# 467444_130_3_2-A.net
KiCad netlist of a schematic drawn in Altium Designer
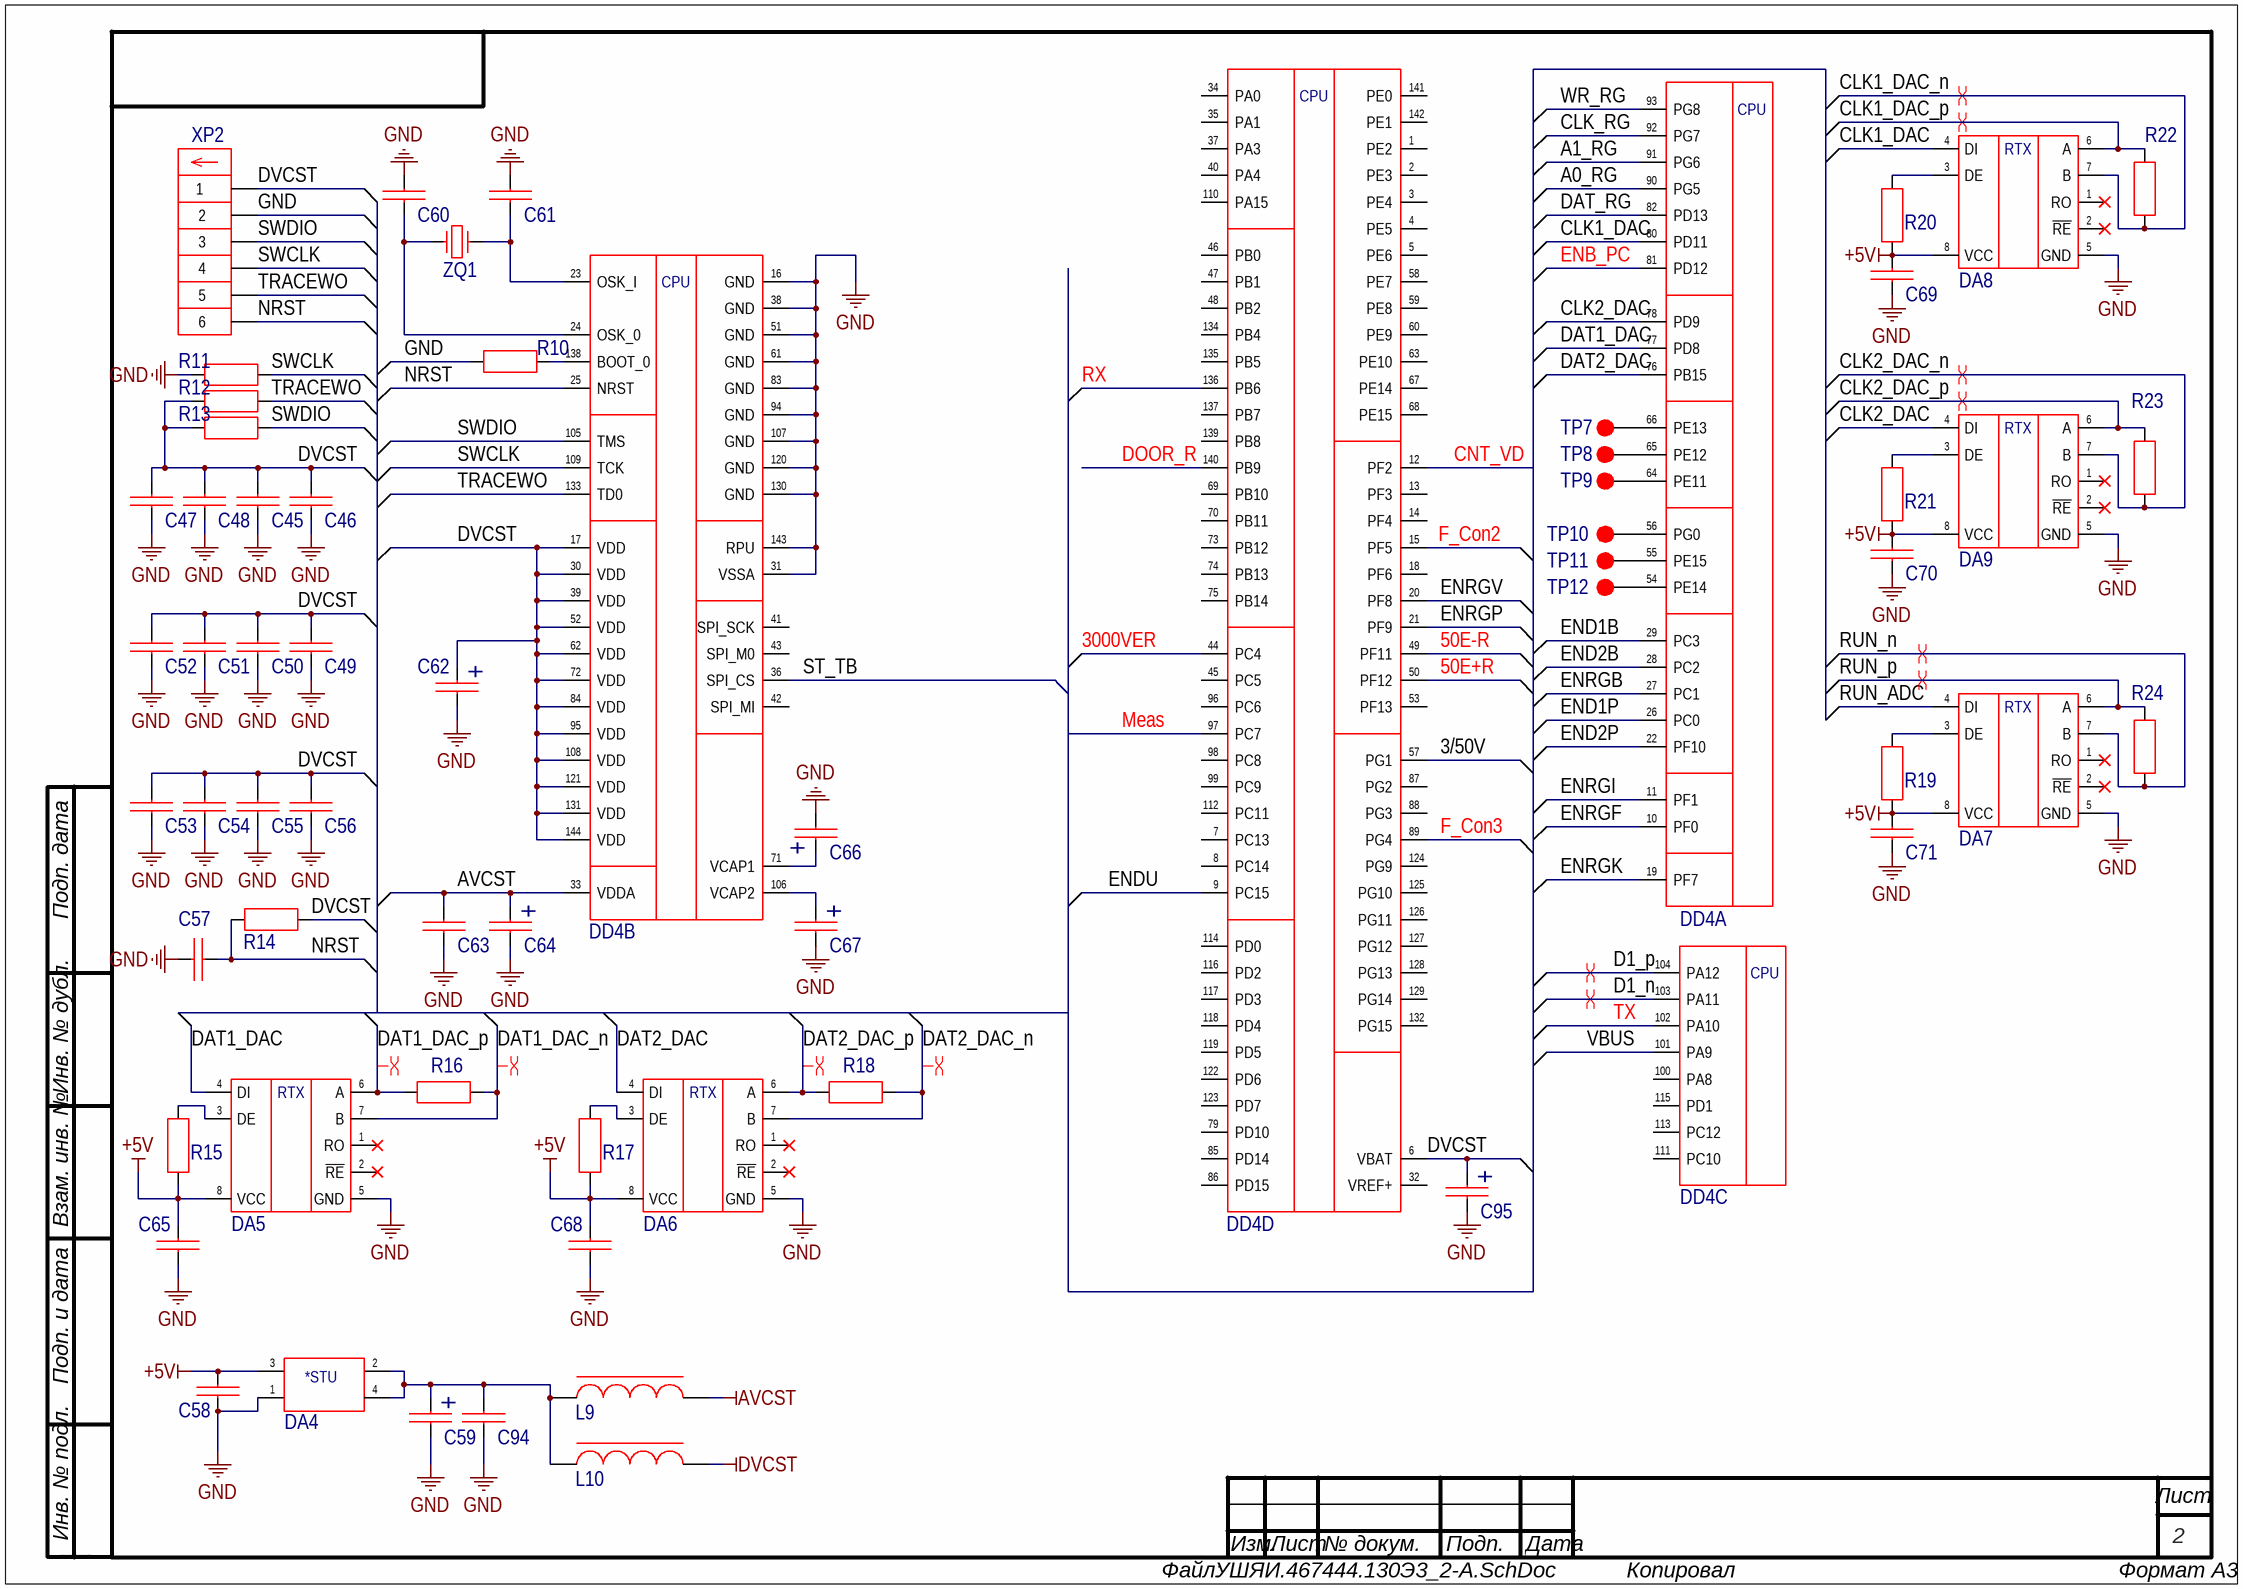
[diagram p0: УШЯИ.467444.130Э3_2-A.SchDoc]

(export (version "E")
  (design (tool "Eeschema 10.0.6"))
  (components
    (comp (ref "C45")
      (value "0,1 µF")
      (footprint "C_0805 [2012 Metric]")
      (description "Неполярный конденсатор")
      (fields (field (name "MANUFACTURER") "Murata") (field (name "VOLTAGE") "50V"))
      (libsource (lib "lib") (part "C_const"))
    )
    (comp (ref "C46")
      (value "0,1 µF")
      (footprint "C_0805 [2012 Metric]")
      (description "Неполярный конденсатор")
      (fields (field (name "MANUFACTURER") "Murata") (field (name "VOLTAGE") "50V"))
      (libsource (lib "lib") (part "C_const"))
    )
    (comp (ref "C47")
      (value "0,1 µF")
      (footprint "C_0805 [2012 Metric]")
      (description "Неполярный конденсатор")
      (fields (field (name "MANUFACTURER") "Murata") (field (name "VOLTAGE") "50V"))
      (libsource (lib "lib") (part "C_const"))
    )
    (comp (ref "C48")
      (value "0,1 µF")
      (footprint "C_0805 [2012 Metric]")
      (description "Неполярный конденсатор")
      (fields (field (name "MANUFACTURER") "Murata") (field (name "VOLTAGE") "50V"))
      (libsource (lib "lib") (part "C_const"))
    )
    (comp (ref "C49")
      (value "0,1 µF")
      (footprint "C_0805 [2012 Metric]")
      (description "Неполярный конденсатор")
      (fields (field (name "MANUFACTURER") "Murata") (field (name "VOLTAGE") "50V"))
      (libsource (lib "lib") (part "C_const"))
    )
    (comp (ref "C50")
      (value "0,1 µF")
      (footprint "C_0805 [2012 Metric]")
      (description "Неполярный конденсатор")
      (fields (field (name "MANUFACTURER") "Murata") (field (name "VOLTAGE") "50V"))
      (libsource (lib "lib") (part "C_const"))
    )
    (comp (ref "C51")
      (value "0,1 µF")
      (footprint "C_0805 [2012 Metric]")
      (description "Неполярный конденсатор")
      (fields (field (name "MANUFACTURER") "Murata") (field (name "VOLTAGE") "50V"))
      (libsource (lib "lib") (part "C_const"))
    )
    (comp (ref "C52")
      (value "0,1 µF")
      (footprint "C_0805 [2012 Metric]")
      (description "Неполярный конденсатор")
      (fields (field (name "MANUFACTURER") "Murata") (field (name "VOLTAGE") "50V"))
      (libsource (lib "lib") (part "C_const"))
    )
    (comp (ref "C53")
      (value "0,1 µF")
      (footprint "C_0805 [2012 Metric]")
      (description "Неполярный конденсатор")
      (fields (field (name "MANUFACTURER") "Murata") (field (name "VOLTAGE") "50V"))
      (libsource (lib "lib") (part "C_const"))
    )
    (comp (ref "C54")
      (value "0,1 µF")
      (footprint "C_0805 [2012 Metric]")
      (description "Неполярный конденсатор")
      (fields (field (name "MANUFACTURER") "Murata") (field (name "VOLTAGE") "50V"))
      (libsource (lib "lib") (part "C_const"))
    )
    (comp (ref "C55")
      (value "0,1 µF")
      (footprint "C_0805 [2012 Metric]")
      (description "Неполярный конденсатор")
      (fields (field (name "MANUFACTURER") "Murata") (field (name "VOLTAGE") "50V"))
      (libsource (lib "lib") (part "C_const"))
    )
    (comp (ref "C56")
      (value "0,1 µF")
      (footprint "C_0805 [2012 Metric]")
      (description "Неполярный конденсатор")
      (fields (field (name "MANUFACTURER") "Murata") (field (name "VOLTAGE") "50V"))
      (libsource (lib "lib") (part "C_const"))
    )
    (comp (ref "C57")
      (value "0,1 µF")
      (footprint "C_0805 [2012 Metric]")
      (description "Неполярный конденсатор")
      (fields (field (name "MANUFACTURER") "Murata") (field (name "VOLTAGE") "50V"))
      (libsource (lib "lib") (part "C_const"))
    )
    (comp (ref "C58")
      (value "0,1 µF")
      (footprint "C_0805 [2012 Metric]")
      (description "Неполярный конденсатор")
      (fields (field (name "MANUFACTURER") "Murata") (field (name "VOLTAGE") "50V"))
      (libsource (lib "lib") (part "C_const"))
    )
    (comp (ref "C59")
      (value "4,7 µF")
      (footprint "C+_1210 [3528-21 Metric]")
      (description "Полярный конденсатор")
      (fields (field (name "MANUFACTURER") "KYOCERA AVX") (field (name "VOLTAGE") "20V\r\n10V"))
      (libsource (lib "lib") (part "C_electrolytic"))
    )
    (comp (ref "C60")
      (value "20 pF")
      (footprint "C_0805 [2012 Metric]")
      (description "Неполярный конденсатор")
      (fields (field (name "MANUFACTURER") "Murata") (field (name "VOLTAGE") "50V"))
      (libsource (lib "lib") (part "C_const"))
    )
    (comp (ref "C61")
      (value "20 pF")
      (footprint "C_0805 [2012 Metric]")
      (description "Неполярный конденсатор")
      (fields (field (name "MANUFACTURER") "Murata") (field (name "VOLTAGE") "50V"))
      (libsource (lib "lib") (part "C_const"))
    )
    (comp (ref "C62")
      (value "10 µF")
      (footprint "C+_1210 [3528-21 Metric]")
      (description "Полярный конденсатор")
      (fields (field (name "MANUFACTURER") "KYOCERA AVX") (field (name "VOLTAGE") "20V\r\n10V"))
      (libsource (lib "lib") (part "C_electrolytic"))
    )
    (comp (ref "C63")
      (value "0,1 µF")
      (footprint "C_0805 [2012 Metric]")
      (description "Неполярный конденсатор")
      (fields (field (name "MANUFACTURER") "Murata") (field (name "VOLTAGE") "50V"))
      (libsource (lib "lib") (part "C_const"))
    )
    (comp (ref "C64")
      (value "10 µF")
      (footprint "C+_1210 [3528-21 Metric]")
      (description "Полярный конденсатор")
      (fields (field (name "MANUFACTURER") "KYOCERA AVX") (field (name "VOLTAGE") "20V\r\n10V"))
      (libsource (lib "lib") (part "C_electrolytic"))
    )
    (comp (ref "C65")
      (value "0,1 µF")
      (footprint "C_0805 [2012 Metric]")
      (description "Неполярный конденсатор")
      (fields (field (name "MANUFACTURER") "Murata") (field (name "VOLTAGE") "50V"))
      (libsource (lib "lib") (part "C_const"))
    )
    (comp (ref "C66")
      (value "2,2 µF")
      (footprint "C+_1206 [3216-18 Metric]")
      (description "Полярный конденсатор")
      (fields (field (name "MANUFACTURER") "AVX") (field (name "VOLTAGE") "16V\r\n10V"))
      (libsource (lib "lib") (part "C_electrolytic"))
    )
    (comp (ref "C67")
      (value "2,2 µF")
      (footprint "C+_1206 [3216-18 Metric]")
      (description "Полярный конденсатор")
      (fields (field (name "MANUFACTURER") "AVX") (field (name "VOLTAGE") "16V\r\n10V"))
      (libsource (lib "lib") (part "C_electrolytic"))
    )
    (comp (ref "C68")
      (value "0,1 µF")
      (footprint "C_0805 [2012 Metric]")
      (description "Неполярный конденсатор")
      (fields (field (name "MANUFACTURER") "Murata") (field (name "VOLTAGE") "50V"))
      (libsource (lib "lib") (part "C_const"))
    )
    (comp (ref "C69")
      (value "0,1 µF")
      (footprint "C_0805 [2012 Metric]")
      (description "Неполярный конденсатор")
      (fields (field (name "MANUFACTURER") "Murata") (field (name "VOLTAGE") "50V"))
      (libsource (lib "lib") (part "C_const"))
    )
    (comp (ref "C70")
      (value "0,1 µF")
      (footprint "C_0805 [2012 Metric]")
      (description "Неполярный конденсатор")
      (fields (field (name "MANUFACTURER") "Murata") (field (name "VOLTAGE") "50V"))
      (libsource (lib "lib") (part "C_const"))
    )
    (comp (ref "C71")
      (value "0,1 µF")
      (footprint "C_0805 [2012 Metric]")
      (description "Неполярный конденсатор")
      (fields (field (name "MANUFACTURER") "Murata") (field (name "VOLTAGE") "50V"))
      (libsource (lib "lib") (part "C_const"))
    )
    (comp (ref "C94")
      (value "0,1 µF")
      (footprint "C_0805 [2012 Metric]")
      (description "Неполярный конденсатор")
      (fields (field (name "MANUFACTURER") "Murata") (field (name "VOLTAGE") "25V"))
      (libsource (lib "lib") (part "C_const"))
    )
    (comp (ref "C95")
      (value "10 µF")
      (footprint "C+_1210 [3528-21 Metric]")
      (description "Полярный конденсатор")
      (fields (field (name "MANUFACTURER") "KYOCERA AVX") (field (name "VOLTAGE") "20V\r\n10V"))
      (libsource (lib "lib") (part "C_electrolytic"))
    )
    (comp (ref "DA4")
      (value "LD1117AS33TR")
      (footprint "SOT-223")
      (description "IC, Fixed LDO Voltage Regulator, 5.3V to 10V, 1.15V Dropout, 3.3Vout, 1Aout")
      (fields (field (name "MANUFACTURER") "STMicroelectronics"))
      (libsource (lib "lib") (part "VolReg_LD1117AS33TR"))
    )
    (comp (ref "DA5")
      (value "ADM483AR")
      (footprint "SOIC-8_1.27_5x4x1.75")
      (description "IC, Transceiver, RS422/RS485, 1 Driver, 1 Receiver, 4.75 V to 5.25 V, -40°C to 125°C")
      (fields (field (name "MANUFACTURER") "Analog Devices"))
      (libsource (lib "lib") (part "ADM483"))
    )
    (comp (ref "DA6")
      (value "ADM483AR")
      (footprint "SOIC-8_1.27_5x4x1.75")
      (description "IC, Transceiver, RS422/RS485, 1 Driver, 1 Receiver, 4.75 V to 5.25 V, -40°C to 125°C")
      (fields (field (name "MANUFACTURER") "Analog Devices"))
      (libsource (lib "lib") (part "ADM483"))
    )
    (comp (ref "DA7")
      (value "ADM483AR")
      (footprint "SOIC-8_1.27_5x4x1.75")
      (description "IC, Transceiver, RS422/RS485, 1 Driver, 1 Receiver, 4.75 V to 5.25 V, -40°C to 125°C")
      (fields (field (name "MANUFACTURER") "Analog Devices"))
      (libsource (lib "lib") (part "ADM483"))
    )
    (comp (ref "DA8")
      (value "ADM483AR")
      (footprint "SOIC-8_1.27_5x4x1.75")
      (description "IC, Transceiver, RS422/RS485, 1 Driver, 1 Receiver, 4.75 V to 5.25 V, -40°C to 125°C")
      (fields (field (name "MANUFACTURER") "Analog Devices"))
      (libsource (lib "lib") (part "ADM483"))
    )
    (comp (ref "DA9")
      (value "ADM483AR")
      (footprint "SOIC-8_1.27_5x4x1.75")
      (description "IC, Transceiver, RS422/RS485, 1 Driver, 1 Receiver, 4.75 V to 5.25 V, -40°C to 125°C")
      (fields (field (name "MANUFACTURER") "Analog Devices"))
      (libsource (lib "lib") (part "ADM483"))
    )
    (comp (ref "DD4")
      (value "STM32F429VIT6STM32F407ZGTx")
      (footprint "QFP-144[20x20]_0.5_22x22x1.6")
      (description "IC, ARM Cortex-M4, 168 MHz, 1 MB ROM, 192 kB RAM, -40°C to 85°C")
      (fields (field (name "MANUFACTURER") "STMicroelectronics"))
      (libsource (lib "") (part "STM32F407_1"))
    )
    (comp (ref "L9")
      (value "~")
      (footprint "IND_0805 [2012 Metric]")
      (fields (field (name "MANUFACTURER") "Vishay") (field (name "TOLERANCE") "±25%"))
      (libsource (lib "lib") (part "IND_ferromagnetic/ferrite_core"))
    )
    (comp (ref "L10")
      (value "~")
      (footprint "IND_0805 [2012 Metric]")
      (fields (field (name "MANUFACTURER") "Vishay") (field (name "TOLERANCE") "±25%"))
      (libsource (lib "lib") (part "IND_ferromagnetic/ferrite_core"))
    )
    (comp (ref "R10")
      (value "10k")
      (footprint "R_0805 [2012 Metric]")
      (fields (field (name "TOLERANCE") "±5%"))
      (libsource (lib "lib") (part "R_Const"))
    )
    (comp (ref "R11")
      (value "10k")
      (footprint "R_0805 [2012 Metric]")
      (fields (field (name "TOLERANCE") "±5%"))
      (libsource (lib "lib") (part "R_Const"))
    )
    (comp (ref "R12")
      (value "10k")
      (footprint "R_0805 [2012 Metric]")
      (fields (field (name "TOLERANCE") "±5%"))
      (libsource (lib "lib") (part "R_Const"))
    )
    (comp (ref "R13")
      (value "10k")
      (footprint "R_0805 [2012 Metric]")
      (fields (field (name "TOLERANCE") "±5%"))
      (libsource (lib "lib") (part "R_Const"))
    )
    (comp (ref "R14")
      (value "10k")
      (footprint "R_0805 [2012 Metric]")
      (fields (field (name "TOLERANCE") "±5%"))
      (libsource (lib "lib") (part "R_Const"))
    )
    (comp (ref "R15")
      (value "10k")
      (footprint "R_0805 [2012 Metric]")
      (fields (field (name "TOLERANCE") "±5%"))
      (libsource (lib "lib") (part "R_Const"))
    )
    (comp (ref "R16")
      (value "100R")
      (footprint "R_0805 [2012 Metric]")
      (fields (field (name "TOLERANCE") "±5%"))
      (libsource (lib "lib") (part "R_Const"))
    )
    (comp (ref "R17")
      (value "10k")
      (footprint "R_0805 [2012 Metric]")
      (fields (field (name "TOLERANCE") "±5%"))
      (libsource (lib "lib") (part "R_Const"))
    )
    (comp (ref "R18")
      (value "100R")
      (footprint "R_0805 [2012 Metric]")
      (fields (field (name "TOLERANCE") "±5%"))
      (libsource (lib "lib") (part "R_Const"))
    )
    (comp (ref "R19")
      (value "10k")
      (footprint "R_0805 [2012 Metric]")
      (fields (field (name "TOLERANCE") "±5%"))
      (libsource (lib "lib") (part "R_Const"))
    )
    (comp (ref "R20")
      (value "10k")
      (footprint "R_0805 [2012 Metric]")
      (fields (field (name "TOLERANCE") "±5%"))
      (libsource (lib "lib") (part "R_Const"))
    )
    (comp (ref "R21")
      (value "10k")
      (footprint "R_0805 [2012 Metric]")
      (fields (field (name "TOLERANCE") "±5%"))
      (libsource (lib "lib") (part "R_Const"))
    )
    (comp (ref "R22")
      (value "100R")
      (footprint "R_0805 [2012 Metric]")
      (fields (field (name "TOLERANCE") "±5%"))
      (libsource (lib "lib") (part "R_Const"))
    )
    (comp (ref "R23")
      (value "100R")
      (footprint "R_0805 [2012 Metric]")
      (fields (field (name "TOLERANCE") "±5%"))
      (libsource (lib "lib") (part "R_Const"))
    )
    (comp (ref "R24")
      (value "100R")
      (footprint "R_0805 [2012 Metric]")
      (fields (field (name "TOLERANCE") "±5%"))
      (libsource (lib "lib") (part "R_Const"))
    )
    (comp (ref "TP7") (value "~") (footprint "DSP_1.3") (libsource (lib "lib") (part "TP")))
    (comp (ref "TP8") (value "~") (footprint "DSP_1.3") (libsource (lib "lib") (part "TP")))
    (comp (ref "TP9") (value "~") (footprint "DSP_1.3") (libsource (lib "lib") (part "TP")))
    (comp (ref "TP10") (value "~") (footprint "DSP_1.3") (libsource (lib "lib") (part "TP")))
    (comp (ref "TP11") (value "~") (footprint "DSP_1.3") (libsource (lib "lib") (part "TP")))
    (comp (ref "TP12") (value "~") (footprint "DSP_1.3") (libsource (lib "lib") (part "TP")))
    (comp (ref "XP2")
      (value "AMPMODU II 280372-2")
      (footprint "AMP II-280372-2")
      (description "Male, 6 pin, 1 row, Vertical, Board-to-Board, 2.54 mm")
      (fields (field (name "MANUFACTURER") "TE Connectivity"))
      (libsource (lib "lib") (part "M_6"))
    )
    (comp (ref "ZQ1")
      (value "Q 25.0JXS63-12-30/30-FU")
      (footprint "JXS63")
      (fields (field (name "MANUFACTURER") "Jauch Quartz GmbH"))
      (libsource (lib "lib") (part "Rezonator_JXS63"))
    )
  )
  (nets
    (net (code "1") (name "+5V") (class "Default")
      (node (ref "C58") (pin "1") (pinfunction "1_1") (pintype "passive"))
      (node (ref "C65") (pin "2") (pinfunction "2_2") (pintype "passive"))
      (node (ref "C68") (pin "2") (pinfunction "2_2") (pintype "passive"))
      (node (ref "C69") (pin "2") (pinfunction "2_2") (pintype "passive"))
      (node (ref "C70") (pin "2") (pinfunction "2_2") (pintype "passive"))
      (node (ref "C71") (pin "2") (pinfunction "2_2") (pintype "passive"))
      (node (ref "DA4") (pin "3") (pinfunction "VIN_3") (pintype "passive"))
      (node (ref "DA5") (pin "8") (pinfunction "VCC_8") (pintype "passive"))
      (node (ref "DA6") (pin "8") (pinfunction "VCC_8") (pintype "passive"))
      (node (ref "DA7") (pin "8") (pinfunction "VCC_8") (pintype "passive"))
      (node (ref "DA8") (pin "8") (pinfunction "VCC_8") (pintype "passive"))
      (node (ref "DA9") (pin "8") (pinfunction "VCC_8") (pintype "passive"))
      (node (ref "R15") (pin "1") (pinfunction "1_1") (pintype "passive"))
      (node (ref "R17") (pin "1") (pinfunction "1_1") (pintype "passive"))
      (node (ref "R19") (pin "1") (pinfunction "1_1") (pintype "passive"))
      (node (ref "R20") (pin "1") (pinfunction "1_1") (pintype "passive"))
      (node (ref "R21") (pin "1") (pinfunction "1_1") (pintype "passive"))
    )
    (net (code "2") (name "/3{slash}50V") (class "Default")
      (node (ref "DD4") (pin "57") (pinfunction "PG1_57") (pintype "passive"))
    )
    (net (code "3") (name "/50E+R") (class "Default")
      (node (ref "DD4") (pin "50") (pinfunction "PF12_50") (pintype "passive"))
    )
    (net (code "4") (name "/50E-R") (class "Default")
      (node (ref "DD4") (pin "49") (pinfunction "PF11_49") (pintype "passive"))
    )
    (net (code "5") (name "/3000VER") (class "Default")
      (node (ref "DD4") (pin "44") (pinfunction "PC4_44") (pintype "passive"))
    )
    (net (code "6") (name "/A0_RG") (class "Default")
      (node (ref "DD4") (pin "90") (pinfunction "PG5_90") (pintype "passive"))
    )
    (net (code "7") (name "/A1_RG") (class "Default")
      (node (ref "DD4") (pin "91") (pinfunction "PG6_91") (pintype "passive"))
    )
    (net (code "8") (name "/CLK1_DAC") (class "Default")
      (node (ref "DA8") (pin "4") (pinfunction "DI_4") (pintype "passive"))
      (node (ref "DD4") (pin "80") (pinfunction "PD11_80") (pintype "passive"))
    )
    (net (code "9") (name "/CLK1_DAC_n") (class "Default")
      (node (ref "DA8") (pin "7") (pinfunction "B_7") (pintype "passive"))
      (node (ref "R22") (pin "1") (pinfunction "1_1") (pintype "passive"))
    )
    (net (code "10") (name "/CLK1_DAC_p") (class "Default")
      (node (ref "DA8") (pin "6") (pinfunction "A_6") (pintype "passive"))
      (node (ref "R22") (pin "2") (pinfunction "2_2") (pintype "passive"))
    )
    (net (code "11") (name "/CLK2_DAC") (class "Default")
      (node (ref "DA9") (pin "4") (pinfunction "DI_4") (pintype "passive"))
      (node (ref "DD4") (pin "78") (pinfunction "PD9_78") (pintype "passive"))
    )
    (net (code "12") (name "/CLK2_DAC_n") (class "Default")
      (node (ref "DA9") (pin "7") (pinfunction "B_7") (pintype "passive"))
      (node (ref "R23") (pin "1") (pinfunction "1_1") (pintype "passive"))
    )
    (net (code "13") (name "/CLK2_DAC_p") (class "Default")
      (node (ref "DA9") (pin "6") (pinfunction "A_6") (pintype "passive"))
      (node (ref "R23") (pin "2") (pinfunction "2_2") (pintype "passive"))
    )
    (net (code "14") (name "/CLK_RG") (class "Default")
      (node (ref "DD4") (pin "92") (pinfunction "PG7_92") (pintype "passive"))
    )
    (net (code "15") (name "/CNT_VD") (class "Default")
      (node (ref "DD4") (pin "12") (pinfunction "PF2_12") (pintype "passive"))
    )
    (net (code "16") (name "/D1_n") (class "Default")
      (node (ref "DD4") (pin "103") (pinfunction "PA11_103") (pintype "passive"))
    )
    (net (code "17") (name "/D1_p") (class "Default")
      (node (ref "DD4") (pin "104") (pinfunction "PA12_104") (pintype "passive"))
    )
    (net (code "18") (name "/DAT1_DAC") (class "Default")
      (node (ref "DA5") (pin "4") (pinfunction "DI_4") (pintype "passive"))
      (node (ref "DD4") (pin "77") (pinfunction "PD8_77") (pintype "passive"))
    )
    (net (code "19") (name "/DAT1_DAC_n") (class "Default")
      (node (ref "DA5") (pin "7") (pinfunction "B_7") (pintype "passive"))
      (node (ref "R16") (pin "2") (pinfunction "2_2") (pintype "passive"))
    )
    (net (code "20") (name "/DAT1_DAC_p") (class "Default")
      (node (ref "DA5") (pin "6") (pinfunction "A_6") (pintype "passive"))
      (node (ref "R16") (pin "1") (pinfunction "1_1") (pintype "passive"))
    )
    (net (code "21") (name "/DAT2_DAC") (class "Default")
      (node (ref "DA6") (pin "4") (pinfunction "DI_4") (pintype "passive"))
      (node (ref "DD4") (pin "76") (pinfunction "PB15_76") (pintype "passive"))
    )
    (net (code "22") (name "/DAT2_DAC_n") (class "Default")
      (node (ref "DA6") (pin "7") (pinfunction "B_7") (pintype "passive"))
      (node (ref "R18") (pin "2") (pinfunction "2_2") (pintype "passive"))
    )
    (net (code "23") (name "/DAT2_DAC_p") (class "Default")
      (node (ref "DA6") (pin "6") (pinfunction "A_6") (pintype "passive"))
      (node (ref "R18") (pin "1") (pinfunction "1_1") (pintype "passive"))
    )
    (net (code "24") (name "/DAT_RG") (class "Default")
      (node (ref "DD4") (pin "82") (pinfunction "PD13_82") (pintype "passive"))
    )
    (net (code "25") (name "/DOOR_R") (class "Default")
      (node (ref "DD4") (pin "140") (pinfunction "PB9_140") (pintype "passive"))
    )
    (net (code "26") (name "/ENB_PC") (class "Default")
      (node (ref "DD4") (pin "81") (pinfunction "PD12_81") (pintype "passive"))
    )
    (net (code "27") (name "/END1B") (class "Default")
      (node (ref "DD4") (pin "29") (pinfunction "PC3_29") (pintype "passive"))
    )
    (net (code "28") (name "/END1P") (class "Default")
      (node (ref "DD4") (pin "26") (pinfunction "PC0_26") (pintype "passive"))
    )
    (net (code "29") (name "/END2B") (class "Default")
      (node (ref "DD4") (pin "28") (pinfunction "PC2_28") (pintype "passive"))
    )
    (net (code "30") (name "/END2P") (class "Default")
      (node (ref "DD4") (pin "22") (pinfunction "PF10_22") (pintype "passive"))
    )
    (net (code "31") (name "/ENDU") (class "Default")
      (node (ref "DD4") (pin "9") (pinfunction "PC15_9") (pintype "passive"))
    )
    (net (code "32") (name "/ENRGB") (class "Default")
      (node (ref "DD4") (pin "27") (pinfunction "PC1_27") (pintype "passive"))
    )
    (net (code "33") (name "/ENRGF") (class "Default")
      (node (ref "DD4") (pin "10") (pinfunction "PF0_10") (pintype "passive"))
    )
    (net (code "34") (name "/ENRGI") (class "Default")
      (node (ref "DD4") (pin "11") (pinfunction "PF1_11") (pintype "passive"))
    )
    (net (code "35") (name "/ENRGK") (class "Default")
      (node (ref "DD4") (pin "19") (pinfunction "PF7_19") (pintype "passive"))
    )
    (net (code "36") (name "/ENRGP") (class "Default")
      (node (ref "DD4") (pin "21") (pinfunction "PF9_21") (pintype "passive"))
    )
    (net (code "37") (name "/ENRGV") (class "Default")
      (node (ref "DD4") (pin "20") (pinfunction "PF8_20") (pintype "passive"))
    )
    (net (code "38") (name "/F_Con2") (class "Default")
      (node (ref "DD4") (pin "15") (pinfunction "PF5_15") (pintype "passive"))
    )
    (net (code "39") (name "/F_Con3") (class "Default")
      (node (ref "DD4") (pin "89") (pinfunction "PG4_89") (pintype "passive"))
    )
    (net (code "40") (name "/Meas") (class "Default")
      (node (ref "DD4") (pin "97") (pinfunction "PC7_97") (pintype "passive"))
    )
    (net (code "41") (name "/NRST") (class "Default")
      (node (ref "C57") (pin "2") (pinfunction "2_2") (pintype "passive"))
      (node (ref "DD4") (pin "25") (pinfunction "NRST_25") (pintype "passive"))
      (node (ref "R14") (pin "2") (pinfunction "2_2") (pintype "passive"))
      (node (ref "XP2") (pin "6") (pinfunction "6_6") (pintype "passive"))
    )
    (net (code "42") (name "/RUN_ADC") (class "Default")
      (node (ref "DA7") (pin "4") (pinfunction "DI_4") (pintype "passive"))
    )
    (net (code "43") (name "/RUN_n") (class "Default")
      (node (ref "DA7") (pin "7") (pinfunction "B_7") (pintype "passive"))
      (node (ref "R24") (pin "1") (pinfunction "1_1") (pintype "passive"))
    )
    (net (code "44") (name "/RUN_p") (class "Default")
      (node (ref "DA7") (pin "6") (pinfunction "A_6") (pintype "passive"))
      (node (ref "R24") (pin "2") (pinfunction "2_2") (pintype "passive"))
    )
    (net (code "45") (name "/RX") (class "Default")
      (node (ref "DD4") (pin "136") (pinfunction "PB6_136") (pintype "passive"))
    )
    (net (code "46") (name "/ST_TB") (class "Default")
      (node (ref "DD4") (pin "36") (pinfunction "SPI_CS_36") (pintype "passive"))
    )
    (net (code "47") (name "/SWCLK") (class "Default")
      (node (ref "DD4") (pin "109") (pinfunction "TCK_109") (pintype "passive"))
      (node (ref "R11") (pin "2") (pinfunction "2_2") (pintype "passive"))
      (node (ref "XP2") (pin "4") (pinfunction "4_4") (pintype "passive"))
    )
    (net (code "48") (name "/SWDIO") (class "Default")
      (node (ref "DD4") (pin "105") (pinfunction "TMS_105") (pintype "passive"))
      (node (ref "R13") (pin "2") (pinfunction "2_2") (pintype "passive"))
      (node (ref "XP2") (pin "3") (pinfunction "3_3") (pintype "passive"))
    )
    (net (code "49") (name "/TRACEWO") (class "Default")
      (node (ref "DD4") (pin "133") (pinfunction "TD0_133") (pintype "passive"))
      (node (ref "R12") (pin "2") (pinfunction "2_2") (pintype "passive"))
      (node (ref "XP2") (pin "5") (pinfunction "5_5") (pintype "passive"))
    )
    (net (code "50") (name "/TX") (class "Default")
      (node (ref "DD4") (pin "102") (pinfunction "PA10_102") (pintype "passive"))
    )
    (net (code "51") (name "/VBUS") (class "Default")
      (node (ref "DD4") (pin "101") (pinfunction "PA9_101") (pintype "passive"))
    )
    (net (code "52") (name "/WR_RG") (class "Default")
      (node (ref "DD4") (pin "93") (pinfunction "PG8_93") (pintype "passive"))
    )
    (net (code "53") (name "AVCST") (class "Default")
      (node (ref "C63") (pin "2") (pinfunction "2_2") (pintype "passive"))
      (node (ref "C64") (pin "+") (pinfunction "+_+") (pintype "passive"))
      (node (ref "DD4") (pin "33") (pinfunction "VDDA_33") (pintype "passive"))
      (node (ref "L9") (pin "2") (pinfunction "2_2") (pintype "passive"))
    )
    (net (code "54") (name "DVCST") (class "Default")
      (node (ref "C45") (pin "2") (pinfunction "2_2") (pintype "passive"))
      (node (ref "C46") (pin "2") (pinfunction "2_2") (pintype "passive"))
      (node (ref "C47") (pin "2") (pinfunction "2_2") (pintype "passive"))
      (node (ref "C48") (pin "2") (pinfunction "2_2") (pintype "passive"))
      (node (ref "C49") (pin "2") (pinfunction "2_2") (pintype "passive"))
      (node (ref "C50") (pin "2") (pinfunction "2_2") (pintype "passive"))
      (node (ref "C51") (pin "2") (pinfunction "2_2") (pintype "passive"))
      (node (ref "C52") (pin "2") (pinfunction "2_2") (pintype "passive"))
      (node (ref "C53") (pin "2") (pinfunction "2_2") (pintype "passive"))
      (node (ref "C54") (pin "2") (pinfunction "2_2") (pintype "passive"))
      (node (ref "C55") (pin "2") (pinfunction "2_2") (pintype "passive"))
      (node (ref "C56") (pin "2") (pinfunction "2_2") (pintype "passive"))
      (node (ref "C62") (pin "+") (pinfunction "+_+") (pintype "passive"))
      (node (ref "C95") (pin "+") (pinfunction "+_+") (pintype "passive"))
      (node (ref "DD4") (pin "108") (pinfunction "VDD_108") (pintype "passive"))
      (node (ref "DD4") (pin "121") (pinfunction "VDD_121") (pintype "passive"))
      (node (ref "DD4") (pin "131") (pinfunction "VDD_131") (pintype "passive"))
      (node (ref "DD4") (pin "144") (pinfunction "VDD_144") (pintype "passive"))
      (node (ref "DD4") (pin "17") (pinfunction "VDD_17") (pintype "passive"))
      (node (ref "DD4") (pin "30") (pinfunction "VDD_30") (pintype "passive"))
      (node (ref "DD4") (pin "39") (pinfunction "VDD_39") (pintype "passive"))
      (node (ref "DD4") (pin "52") (pinfunction "VDD_52") (pintype "passive"))
      (node (ref "DD4") (pin "6") (pinfunction "VBAT_6") (pintype "passive"))
      (node (ref "DD4") (pin "62") (pinfunction "VDD_62") (pintype "passive"))
      (node (ref "DD4") (pin "72") (pinfunction "VDD_72") (pintype "passive"))
      (node (ref "DD4") (pin "84") (pinfunction "VDD_84") (pintype "passive"))
      (node (ref "DD4") (pin "95") (pinfunction "VDD_95") (pintype "passive"))
      (node (ref "L10") (pin "2") (pinfunction "2_2") (pintype "passive"))
      (node (ref "R12") (pin "1") (pinfunction "1_1") (pintype "passive"))
      (node (ref "R13") (pin "1") (pinfunction "1_1") (pintype "passive"))
      (node (ref "R14") (pin "1") (pinfunction "1_1") (pintype "passive"))
      (node (ref "XP2") (pin "1") (pinfunction "1_1") (pintype "passive"))
    )
    (net (code "55") (name "GND") (class "Default")
      (node (ref "C45") (pin "1") (pinfunction "1_1") (pintype "passive"))
      (node (ref "C46") (pin "1") (pinfunction "1_1") (pintype "passive"))
      (node (ref "C47") (pin "1") (pinfunction "1_1") (pintype "passive"))
      (node (ref "C48") (pin "1") (pinfunction "1_1") (pintype "passive"))
      (node (ref "C49") (pin "1") (pinfunction "1_1") (pintype "passive"))
      (node (ref "C50") (pin "1") (pinfunction "1_1") (pintype "passive"))
      (node (ref "C51") (pin "1") (pinfunction "1_1") (pintype "passive"))
      (node (ref "C52") (pin "1") (pinfunction "1_1") (pintype "passive"))
      (node (ref "C53") (pin "1") (pinfunction "1_1") (pintype "passive"))
      (node (ref "C54") (pin "1") (pinfunction "1_1") (pintype "passive"))
      (node (ref "C55") (pin "1") (pinfunction "1_1") (pintype "passive"))
      (node (ref "C56") (pin "1") (pinfunction "1_1") (pintype "passive"))
      (node (ref "C57") (pin "1") (pinfunction "1_1") (pintype "passive"))
      (node (ref "C58") (pin "2") (pinfunction "2_2") (pintype "passive"))
      (node (ref "C59") (pin "-") (pinfunction "-_-") (pintype "passive"))
      (node (ref "C60") (pin "2") (pinfunction "2_2") (pintype "passive"))
      (node (ref "C61") (pin "2") (pinfunction "2_2") (pintype "passive"))
      (node (ref "C62") (pin "-") (pinfunction "-_-") (pintype "passive"))
      (node (ref "C63") (pin "1") (pinfunction "1_1") (pintype "passive"))
      (node (ref "C64") (pin "-") (pinfunction "-_-") (pintype "passive"))
      (node (ref "C65") (pin "1") (pinfunction "1_1") (pintype "passive"))
      (node (ref "C66") (pin "-") (pinfunction "-_-") (pintype "passive"))
      (node (ref "C67") (pin "-") (pinfunction "-_-") (pintype "passive"))
      (node (ref "C68") (pin "1") (pinfunction "1_1") (pintype "passive"))
      (node (ref "C69") (pin "1") (pinfunction "1_1") (pintype "passive"))
      (node (ref "C70") (pin "1") (pinfunction "1_1") (pintype "passive"))
      (node (ref "C71") (pin "1") (pinfunction "1_1") (pintype "passive"))
      (node (ref "C94") (pin "1") (pinfunction "1_1") (pintype "passive"))
      (node (ref "C95") (pin "-") (pinfunction "-_-") (pintype "passive"))
      (node (ref "DA4") (pin "1") (pinfunction "ADJ/GND_1") (pintype "passive"))
      (node (ref "DA5") (pin "5") (pinfunction "GND_5") (pintype "passive"))
      (node (ref "DA6") (pin "5") (pinfunction "GND_5") (pintype "passive"))
      (node (ref "DA7") (pin "5") (pinfunction "GND_5") (pintype "passive"))
      (node (ref "DA8") (pin "5") (pinfunction "GND_5") (pintype "passive"))
      (node (ref "DA9") (pin "5") (pinfunction "GND_5") (pintype "passive"))
      (node (ref "DD4") (pin "107") (pinfunction "GND_107") (pintype "passive"))
      (node (ref "DD4") (pin "120") (pinfunction "GND_120") (pintype "passive"))
      (node (ref "DD4") (pin "130") (pinfunction "GND_130") (pintype "passive"))
      (node (ref "DD4") (pin "143") (pinfunction "RPU_143") (pintype "passive"))
      (node (ref "DD4") (pin "16") (pinfunction "GND_16") (pintype "passive"))
      (node (ref "DD4") (pin "31") (pinfunction "VSSA_31") (pintype "passive"))
      (node (ref "DD4") (pin "38") (pinfunction "GND_38") (pintype "passive"))
      (node (ref "DD4") (pin "51") (pinfunction "GND_51") (pintype "passive"))
      (node (ref "DD4") (pin "61") (pinfunction "GND_61") (pintype "passive"))
      (node (ref "DD4") (pin "83") (pinfunction "GND_83") (pintype "passive"))
      (node (ref "DD4") (pin "94") (pinfunction "GND_94") (pintype "passive"))
      (node (ref "R10") (pin "1") (pinfunction "1_1") (pintype "passive"))
      (node (ref "R11") (pin "1") (pinfunction "1_1") (pintype "passive"))
      (node (ref "XP2") (pin "2") (pinfunction "2_2") (pintype "passive"))
    )
    (net (code "56") (name "Net-(C59-Pad+)") (class "Default")
      (node (ref "C59") (pin "+") (pinfunction "+_+") (pintype "passive"))
      (node (ref "C94") (pin "2") (pinfunction "2_2") (pintype "passive"))
      (node (ref "DA4") (pin "2") (pinfunction "VOUT_2") (pintype "passive"))
      (node (ref "DA4") (pin "4") (pinfunction "VOUT_4") (pintype "passive"))
      (node (ref "L10") (pin "1") (pinfunction "1_1") (pintype "passive"))
      (node (ref "L9") (pin "1") (pinfunction "1_1") (pintype "passive"))
    )
    (net (code "57") (name "Net-(DA5-DE)") (class "Default")
      (node (ref "DA5") (pin "3") (pinfunction "DE_3") (pintype "passive"))
      (node (ref "R15") (pin "2") (pinfunction "2_2") (pintype "passive"))
    )
    (net (code "58") (name "Net-(DA6-DE)") (class "Default")
      (node (ref "DA6") (pin "3") (pinfunction "DE_3") (pintype "passive"))
      (node (ref "R17") (pin "2") (pinfunction "2_2") (pintype "passive"))
    )
    (net (code "59") (name "Net-(DA7-DE)") (class "Default")
      (node (ref "DA7") (pin "3") (pinfunction "DE_3") (pintype "passive"))
      (node (ref "R19") (pin "2") (pinfunction "2_2") (pintype "passive"))
    )
    (net (code "60") (name "Net-(DA8-DE)") (class "Default")
      (node (ref "DA8") (pin "3") (pinfunction "DE_3") (pintype "passive"))
      (node (ref "R20") (pin "2") (pinfunction "2_2") (pintype "passive"))
    )
    (net (code "61") (name "Net-(DA9-DE)") (class "Default")
      (node (ref "DA9") (pin "3") (pinfunction "DE_3") (pintype "passive"))
      (node (ref "R21") (pin "2") (pinfunction "2_2") (pintype "passive"))
    )
    (net (code "62") (name "Net-(DD4A-PE11)") (class "Default")
      (node (ref "DD4") (pin "64") (pinfunction "PE11_64") (pintype "passive"))
      (node (ref "TP9") (pin "1") (pinfunction "1_1") (pintype "passive"))
    )
    (net (code "63") (name "Net-(DD4A-PE12)") (class "Default")
      (node (ref "DD4") (pin "65") (pinfunction "PE12_65") (pintype "passive"))
      (node (ref "TP8") (pin "1") (pinfunction "1_1") (pintype "passive"))
    )
    (net (code "64") (name "Net-(DD4A-PE13)") (class "Default")
      (node (ref "DD4") (pin "66") (pinfunction "PE13_66") (pintype "passive"))
      (node (ref "TP7") (pin "1") (pinfunction "1_1") (pintype "passive"))
    )
    (net (code "65") (name "Net-(DD4A-PE14)") (class "Default")
      (node (ref "DD4") (pin "54") (pinfunction "PE14_54") (pintype "passive"))
      (node (ref "TP12") (pin "1") (pinfunction "1_1") (pintype "passive"))
    )
    (net (code "66") (name "Net-(DD4A-PE15)") (class "Default")
      (node (ref "DD4") (pin "55") (pinfunction "PE15_55") (pintype "passive"))
      (node (ref "TP11") (pin "1") (pinfunction "1_1") (pintype "passive"))
    )
    (net (code "67") (name "Net-(DD4A-PG0)") (class "Default")
      (node (ref "DD4") (pin "56") (pinfunction "PG0_56") (pintype "passive"))
      (node (ref "TP10") (pin "1") (pinfunction "1_1") (pintype "passive"))
    )
    (net (code "68") (name "Net-(DD4B-BOOT_0)") (class "Default")
      (node (ref "DD4") (pin "138") (pinfunction "BOOT_0_138") (pintype "passive"))
      (node (ref "R10") (pin "2") (pinfunction "2_2") (pintype "passive"))
    )
    (net (code "69") (name "Net-(DD4B-OSK_0)") (class "Default")
      (node (ref "C60") (pin "1") (pinfunction "1_1") (pintype "passive"))
      (node (ref "DD4") (pin "24") (pinfunction "OSK_0_24") (pintype "passive"))
      (node (ref "ZQ1") (pin "1") (pinfunction "1_1") (pintype "passive"))
    )
    (net (code "70") (name "Net-(DD4B-OSK_I)") (class "Default")
      (node (ref "C61") (pin "1") (pinfunction "1_1") (pintype "passive"))
      (node (ref "DD4") (pin "23") (pinfunction "OSK_I_23") (pintype "passive"))
      (node (ref "ZQ1") (pin "3") (pinfunction "3_3") (pintype "passive"))
    )
    (net (code "71") (name "Net-(DD4B-VCAP1)") (class "Default")
      (node (ref "C66") (pin "+") (pinfunction "+_+") (pintype "passive"))
      (node (ref "DD4") (pin "71") (pinfunction "VCAP1_71") (pintype "passive"))
    )
    (net (code "72") (name "Net-(DD4B-VCAP2)") (class "Default")
      (node (ref "C67") (pin "+") (pinfunction "+_+") (pintype "passive"))
      (node (ref "DD4") (pin "106") (pinfunction "VCAP2_106") (pintype "passive"))
    )
    (net (code "73") (name "unconnected-(DA5-RO-Pad1)") (class "Default")
      (node (ref "DA5") (pin "1") (pinfunction "RO_1") (pintype "passive+no_connect"))
    )
    (net (code "74") (name "unconnected-(DA5-~{RE}-Pad2)") (class "Default")
      (node (ref "DA5") (pin "2") (pinfunction "~{RE}_2") (pintype "passive+no_connect"))
    )
    (net (code "75") (name "unconnected-(DA6-RO-Pad1)") (class "Default")
      (node (ref "DA6") (pin "1") (pinfunction "RO_1") (pintype "passive+no_connect"))
    )
    (net (code "76") (name "unconnected-(DA6-~{RE}-Pad2)") (class "Default")
      (node (ref "DA6") (pin "2") (pinfunction "~{RE}_2") (pintype "passive+no_connect"))
    )
    (net (code "77") (name "unconnected-(DA7-RO-Pad1)") (class "Default")
      (node (ref "DA7") (pin "1") (pinfunction "RO_1") (pintype "passive+no_connect"))
    )
    (net (code "78") (name "unconnected-(DA7-~{RE}-Pad2)") (class "Default")
      (node (ref "DA7") (pin "2") (pinfunction "~{RE}_2") (pintype "passive+no_connect"))
    )
    (net (code "79") (name "unconnected-(DA8-RO-Pad1)") (class "Default")
      (node (ref "DA8") (pin "1") (pinfunction "RO_1") (pintype "passive+no_connect"))
    )
    (net (code "80") (name "unconnected-(DA8-~{RE}-Pad2)") (class "Default")
      (node (ref "DA8") (pin "2") (pinfunction "~{RE}_2") (pintype "passive+no_connect"))
    )
    (net (code "81") (name "unconnected-(DA9-RO-Pad1)") (class "Default")
      (node (ref "DA9") (pin "1") (pinfunction "RO_1") (pintype "passive+no_connect"))
    )
    (net (code "82") (name "unconnected-(DA9-~{RE}-Pad2)") (class "Default")
      (node (ref "DA9") (pin "2") (pinfunction "~{RE}_2") (pintype "passive+no_connect"))
    )
    (net (code "83") (name "unconnected-(DD4B-SPI_M0-Pad43)") (class "Default")
      (node (ref "DD4") (pin "43") (pinfunction "SPI_M0_43") (pintype "passive"))
    )
    (net (code "84") (name "unconnected-(DD4B-SPI_MI-Pad42)") (class "Default")
      (node (ref "DD4") (pin "42") (pinfunction "SPI_MI_42") (pintype "passive"))
    )
    (net (code "85") (name "unconnected-(DD4B-SPI_SCK-Pad41)") (class "Default")
      (node (ref "DD4") (pin "41") (pinfunction "SPI_SCK_41") (pintype "passive"))
    )
    (net (code "86") (name "unconnected-(DD4C-PA8-Pad100)") (class "Default")
      (node (ref "DD4") (pin "100") (pinfunction "PA8_100") (pintype "passive"))
    )
    (net (code "87") (name "unconnected-(DD4C-PC10-Pad111)") (class "Default")
      (node (ref "DD4") (pin "111") (pinfunction "PC10_111") (pintype "passive"))
    )
    (net (code "88") (name "unconnected-(DD4C-PC12-Pad113)") (class "Default")
      (node (ref "DD4") (pin "113") (pinfunction "PC12_113") (pintype "passive"))
    )
    (net (code "89") (name "unconnected-(DD4C-PD1-Pad115)") (class "Default")
      (node (ref "DD4") (pin "115") (pinfunction "PD1_115") (pintype "passive"))
    )
    (net (code "90") (name "unconnected-(DD4D-PA0-Pad34)") (class "Default")
      (node (ref "DD4") (pin "34") (pinfunction "PA0_34") (pintype "passive"))
    )
    (net (code "91") (name "unconnected-(DD4D-PA1-Pad35)") (class "Default")
      (node (ref "DD4") (pin "35") (pinfunction "PA1_35") (pintype "passive"))
    )
    (net (code "92") (name "unconnected-(DD4D-PA3-Pad37)") (class "Default")
      (node (ref "DD4") (pin "37") (pinfunction "PA3_37") (pintype "passive"))
    )
    (net (code "93") (name "unconnected-(DD4D-PA4-Pad40)") (class "Default")
      (node (ref "DD4") (pin "40") (pinfunction "PA4_40") (pintype "passive"))
    )
    (net (code "94") (name "unconnected-(DD4D-PA15-Pad110)") (class "Default")
      (node (ref "DD4") (pin "110") (pinfunction "PA15_110") (pintype "passive"))
    )
    (net (code "95") (name "unconnected-(DD4D-PB0-Pad46)") (class "Default")
      (node (ref "DD4") (pin "46") (pinfunction "PB0_46") (pintype "passive"))
    )
    (net (code "96") (name "unconnected-(DD4D-PB1-Pad47)") (class "Default")
      (node (ref "DD4") (pin "47") (pinfunction "PB1_47") (pintype "passive"))
    )
    (net (code "97") (name "unconnected-(DD4D-PB2-Pad48)") (class "Default")
      (node (ref "DD4") (pin "48") (pinfunction "PB2_48") (pintype "passive"))
    )
    (net (code "98") (name "unconnected-(DD4D-PB4-Pad134)") (class "Default")
      (node (ref "DD4") (pin "134") (pinfunction "PB4_134") (pintype "passive"))
    )
    (net (code "99") (name "unconnected-(DD4D-PB5-Pad135)") (class "Default")
      (node (ref "DD4") (pin "135") (pinfunction "PB5_135") (pintype "passive"))
    )
    (net (code "100") (name "unconnected-(DD4D-PB7-Pad137)") (class "Default")
      (node (ref "DD4") (pin "137") (pinfunction "PB7_137") (pintype "passive"))
    )
    (net (code "101") (name "unconnected-(DD4D-PB8-Pad139)") (class "Default")
      (node (ref "DD4") (pin "139") (pinfunction "PB8_139") (pintype "passive"))
    )
    (net (code "102") (name "unconnected-(DD4D-PB10-Pad69)") (class "Default")
      (node (ref "DD4") (pin "69") (pinfunction "PB10_69") (pintype "passive"))
    )
    (net (code "103") (name "unconnected-(DD4D-PB11-Pad70)") (class "Default")
      (node (ref "DD4") (pin "70") (pinfunction "PB11_70") (pintype "passive"))
    )
    (net (code "104") (name "unconnected-(DD4D-PB12-Pad73)") (class "Default")
      (node (ref "DD4") (pin "73") (pinfunction "PB12_73") (pintype "passive"))
    )
    (net (code "105") (name "unconnected-(DD4D-PB13-Pad74)") (class "Default")
      (node (ref "DD4") (pin "74") (pinfunction "PB13_74") (pintype "passive"))
    )
    (net (code "106") (name "unconnected-(DD4D-PB14-Pad75)") (class "Default")
      (node (ref "DD4") (pin "75") (pinfunction "PB14_75") (pintype "passive"))
    )
    (net (code "107") (name "unconnected-(DD4D-PC5-Pad45)") (class "Default")
      (node (ref "DD4") (pin "45") (pinfunction "PC5_45") (pintype "passive"))
    )
    (net (code "108") (name "unconnected-(DD4D-PC6-Pad96)") (class "Default")
      (node (ref "DD4") (pin "96") (pinfunction "PC6_96") (pintype "passive"))
    )
    (net (code "109") (name "unconnected-(DD4D-PC8-Pad98)") (class "Default")
      (node (ref "DD4") (pin "98") (pinfunction "PC8_98") (pintype "passive"))
    )
    (net (code "110") (name "unconnected-(DD4D-PC9-Pad99)") (class "Default")
      (node (ref "DD4") (pin "99") (pinfunction "PC9_99") (pintype "passive"))
    )
    (net (code "111") (name "unconnected-(DD4D-PC11-Pad112)") (class "Default")
      (node (ref "DD4") (pin "112") (pinfunction "PC11_112") (pintype "passive"))
    )
    (net (code "112") (name "unconnected-(DD4D-PC13-Pad7)") (class "Default")
      (node (ref "DD4") (pin "7") (pinfunction "PC13_7") (pintype "passive"))
    )
    (net (code "113") (name "unconnected-(DD4D-PC14-Pad8)") (class "Default")
      (node (ref "DD4") (pin "8") (pinfunction "PC14_8") (pintype "passive"))
    )
    (net (code "114") (name "unconnected-(DD4D-PD0-Pad114)") (class "Default")
      (node (ref "DD4") (pin "114") (pinfunction "PD0_114") (pintype "passive"))
    )
    (net (code "115") (name "unconnected-(DD4D-PD2-Pad116)") (class "Default")
      (node (ref "DD4") (pin "116") (pinfunction "PD2_116") (pintype "passive"))
    )
    (net (code "116") (name "unconnected-(DD4D-PD3-Pad117)") (class "Default")
      (node (ref "DD4") (pin "117") (pinfunction "PD3_117") (pintype "passive"))
    )
    (net (code "117") (name "unconnected-(DD4D-PD4-Pad118)") (class "Default")
      (node (ref "DD4") (pin "118") (pinfunction "PD4_118") (pintype "passive"))
    )
    (net (code "118") (name "unconnected-(DD4D-PD5-Pad119)") (class "Default")
      (node (ref "DD4") (pin "119") (pinfunction "PD5_119") (pintype "passive"))
    )
    (net (code "119") (name "unconnected-(DD4D-PD6-Pad122)") (class "Default")
      (node (ref "DD4") (pin "122") (pinfunction "PD6_122") (pintype "passive"))
    )
    (net (code "120") (name "unconnected-(DD4D-PD7-Pad123)") (class "Default")
      (node (ref "DD4") (pin "123") (pinfunction "PD7_123") (pintype "passive"))
    )
    (net (code "121") (name "unconnected-(DD4D-PD10-Pad79)") (class "Default")
      (node (ref "DD4") (pin "79") (pinfunction "PD10_79") (pintype "passive"))
    )
    (net (code "122") (name "unconnected-(DD4D-PD14-Pad85)") (class "Default")
      (node (ref "DD4") (pin "85") (pinfunction "PD14_85") (pintype "passive"))
    )
    (net (code "123") (name "unconnected-(DD4D-PD15-Pad86)") (class "Default")
      (node (ref "DD4") (pin "86") (pinfunction "PD15_86") (pintype "passive"))
    )
    (net (code "124") (name "unconnected-(DD4D-PE0-Pad141)") (class "Default")
      (node (ref "DD4") (pin "141") (pinfunction "PE0_141") (pintype "passive"))
    )
    (net (code "125") (name "unconnected-(DD4D-PE1-Pad142)") (class "Default")
      (node (ref "DD4") (pin "142") (pinfunction "PE1_142") (pintype "passive"))
    )
    (net (code "126") (name "unconnected-(DD4D-PE2-Pad1)") (class "Default")
      (node (ref "DD4") (pin "1") (pinfunction "PE2_1") (pintype "passive"))
    )
    (net (code "127") (name "unconnected-(DD4D-PE3-Pad2)") (class "Default")
      (node (ref "DD4") (pin "2") (pinfunction "PE3_2") (pintype "passive"))
    )
    (net (code "128") (name "unconnected-(DD4D-PE4-Pad3)") (class "Default")
      (node (ref "DD4") (pin "3") (pinfunction "PE4_3") (pintype "passive"))
    )
    (net (code "129") (name "unconnected-(DD4D-PE5-Pad4)") (class "Default")
      (node (ref "DD4") (pin "4") (pinfunction "PE5_4") (pintype "passive"))
    )
    (net (code "130") (name "unconnected-(DD4D-PE6-Pad5)") (class "Default")
      (node (ref "DD4") (pin "5") (pinfunction "PE6_5") (pintype "passive"))
    )
    (net (code "131") (name "unconnected-(DD4D-PE7-Pad58)") (class "Default")
      (node (ref "DD4") (pin "58") (pinfunction "PE7_58") (pintype "passive"))
    )
    (net (code "132") (name "unconnected-(DD4D-PE8-Pad59)") (class "Default")
      (node (ref "DD4") (pin "59") (pinfunction "PE8_59") (pintype "passive"))
    )
    (net (code "133") (name "unconnected-(DD4D-PE9-Pad60)") (class "Default")
      (node (ref "DD4") (pin "60") (pinfunction "PE9_60") (pintype "passive"))
    )
    (net (code "134") (name "unconnected-(DD4D-PE10-Pad63)") (class "Default")
      (node (ref "DD4") (pin "63") (pinfunction "PE10_63") (pintype "passive"))
    )
    (net (code "135") (name "unconnected-(DD4D-PE14-Pad67)") (class "Default")
      (node (ref "DD4") (pin "67") (pinfunction "PE14_67") (pintype "passive"))
    )
    (net (code "136") (name "unconnected-(DD4D-PE15-Pad68)") (class "Default")
      (node (ref "DD4") (pin "68") (pinfunction "PE15_68") (pintype "passive"))
    )
    (net (code "137") (name "unconnected-(DD4D-PF3-Pad13)") (class "Default")
      (node (ref "DD4") (pin "13") (pinfunction "PF3_13") (pintype "passive"))
    )
    (net (code "138") (name "unconnected-(DD4D-PF4-Pad14)") (class "Default")
      (node (ref "DD4") (pin "14") (pinfunction "PF4_14") (pintype "passive"))
    )
    (net (code "139") (name "unconnected-(DD4D-PF6-Pad18)") (class "Default")
      (node (ref "DD4") (pin "18") (pinfunction "PF6_18") (pintype "passive"))
    )
    (net (code "140") (name "unconnected-(DD4D-PF13-Pad53)") (class "Default")
      (node (ref "DD4") (pin "53") (pinfunction "PF13_53") (pintype "passive"))
    )
    (net (code "141") (name "unconnected-(DD4D-PG2-Pad87)") (class "Default")
      (node (ref "DD4") (pin "87") (pinfunction "PG2_87") (pintype "passive"))
    )
    (net (code "142") (name "unconnected-(DD4D-PG3-Pad88)") (class "Default")
      (node (ref "DD4") (pin "88") (pinfunction "PG3_88") (pintype "passive"))
    )
    (net (code "143") (name "unconnected-(DD4D-PG9-Pad124)") (class "Default")
      (node (ref "DD4") (pin "124") (pinfunction "PG9_124") (pintype "passive"))
    )
    (net (code "144") (name "unconnected-(DD4D-PG10-Pad125)") (class "Default")
      (node (ref "DD4") (pin "125") (pinfunction "PG10_125") (pintype "passive"))
    )
    (net (code "145") (name "unconnected-(DD4D-PG11-Pad126)") (class "Default")
      (node (ref "DD4") (pin "126") (pinfunction "PG11_126") (pintype "passive"))
    )
    (net (code "146") (name "unconnected-(DD4D-PG12-Pad127)") (class "Default")
      (node (ref "DD4") (pin "127") (pinfunction "PG12_127") (pintype "passive"))
    )
    (net (code "147") (name "unconnected-(DD4D-PG13-Pad128)") (class "Default")
      (node (ref "DD4") (pin "128") (pinfunction "PG13_128") (pintype "passive"))
    )
    (net (code "148") (name "unconnected-(DD4D-PG14-Pad129)") (class "Default")
      (node (ref "DD4") (pin "129") (pinfunction "PG14_129") (pintype "passive"))
    )
    (net (code "149") (name "unconnected-(DD4D-PG15-Pad132)") (class "Default")
      (node (ref "DD4") (pin "132") (pinfunction "PG15_132") (pintype "passive"))
    )
    (net (code "150") (name "unconnected-(DD4D-VREF+-Pad32)") (class "Default")
      (node (ref "DD4") (pin "32") (pinfunction "VREF+_32") (pintype "passive"))
    )
  )
)
